# gamby.net
KiCad netlist of a schematic drawn in EAGLE
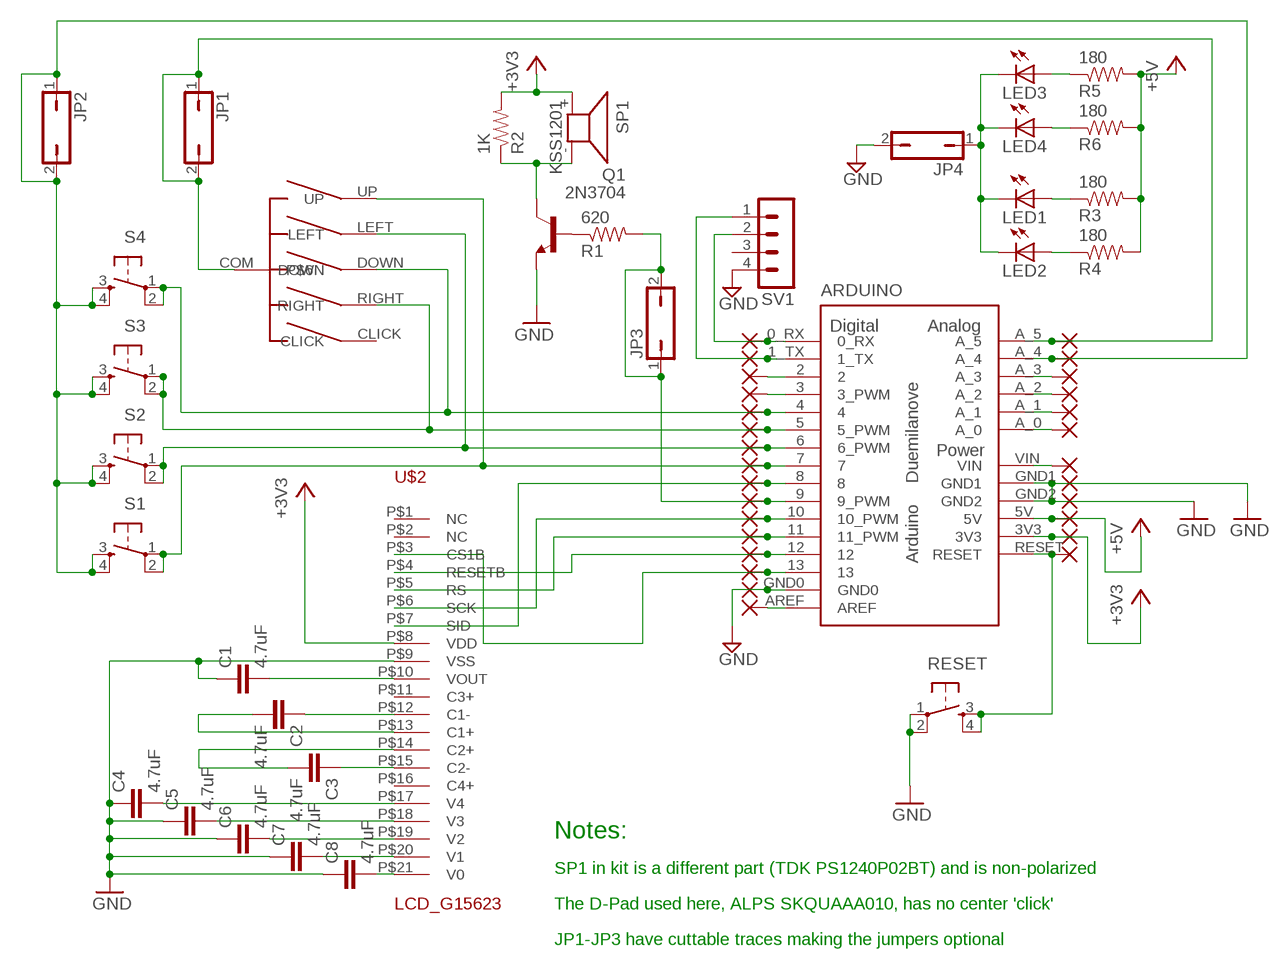
[diagram p0: schematic, sheet 1]

(export (version "E")
  (design (tool "Eeschema 10.0.6"))
  (components
    (comp (ref "ARDUINO")
      (value "ARDUINO-USBLONG_PADS_TEXT")
      (footprint "eagle-import:SHIELD")
      (libsource (lib "eagle-import") (part "ARDUINO-USBLONG_PADS_TEXT"))
    )
    (comp (ref "C1")
      (value "4.7uF")
      (footprint "eagle-import:C2.5-2")
      (libsource (lib "eagle-import") (part "C2.5/2"))
    )
    (comp (ref "C2")
      (value "4.7uF")
      (footprint "eagle-import:C2.5-2")
      (libsource (lib "eagle-import") (part "C2.5/2"))
    )
    (comp (ref "C3")
      (value "4.7uF")
      (footprint "eagle-import:C2.5-2")
      (libsource (lib "eagle-import") (part "C2.5/2"))
    )
    (comp (ref "C4")
      (value "4.7uF")
      (footprint "eagle-import:C2.5-2")
      (libsource (lib "eagle-import") (part "C2.5/2"))
    )
    (comp (ref "C5")
      (value "4.7uF")
      (footprint "eagle-import:C2.5-2")
      (libsource (lib "eagle-import") (part "C2.5/2"))
    )
    (comp (ref "C6")
      (value "4.7uF")
      (footprint "eagle-import:C2.5-2")
      (libsource (lib "eagle-import") (part "C2.5/2"))
    )
    (comp (ref "C7")
      (value "4.7uF")
      (footprint "eagle-import:C2.5-2")
      (libsource (lib "eagle-import") (part "C2.5/2"))
    )
    (comp (ref "C8")
      (value "4.7uF")
      (footprint "eagle-import:C2.5-2")
      (libsource (lib "eagle-import") (part "C2.5/2"))
    )
    (comp (ref "JP1")
      (value "JP1Q")
      (footprint "eagle-import:JP1")
      (libsource (lib "eagle-import") (part "JP1Q"))
    )
    (comp (ref "JP2")
      (value "JP1Q")
      (footprint "eagle-import:JP1")
      (libsource (lib "eagle-import") (part "JP1Q"))
    )
    (comp (ref "JP3")
      (value "JP1Q")
      (footprint "eagle-import:JP1")
      (libsource (lib "eagle-import") (part "JP1Q"))
    )
    (comp (ref "JP4")
      (value "JP1Q")
      (footprint "eagle-import:JP1")
      (libsource (lib "eagle-import") (part "JP1Q"))
    )
    (comp (ref "LED1")
      (value "LEDSMT1206")
      (footprint "eagle-import:1206")
      (libsource (lib "eagle-import") (part "LEDSMT1206"))
    )
    (comp (ref "LED2")
      (value "LEDSMT1206")
      (footprint "eagle-import:1206")
      (libsource (lib "eagle-import") (part "LEDSMT1206"))
    )
    (comp (ref "LED3")
      (value "LEDSMT1206")
      (footprint "eagle-import:1206")
      (libsource (lib "eagle-import") (part "LEDSMT1206"))
    )
    (comp (ref "LED4")
      (value "LEDSMT1206")
      (footprint "eagle-import:1206")
      (libsource (lib "eagle-import") (part "LEDSMT1206"))
    )
    (comp (ref "PAD_3V3")
      (value "WIREPAD1,6/0,9")
      (footprint "eagle-import:1,6_0,9")
      (libsource (lib "eagle-import") (part "WIREPAD1,6/0,9"))
    )
    (comp (ref "PAD_5V")
      (value "WIREPAD1,6/0,9")
      (footprint "eagle-import:1,6_0,9")
      (libsource (lib "eagle-import") (part "WIREPAD1,6/0,9"))
    )
    (comp (ref "PAD_A0")
      (value "WIREPAD1,6/0,9")
      (footprint "eagle-import:1,6_0,9")
      (libsource (lib "eagle-import") (part "WIREPAD1,6/0,9"))
    )
    (comp (ref "PAD_A1")
      (value "WIREPAD1,6/0,9")
      (footprint "eagle-import:1,6_0,9")
      (libsource (lib "eagle-import") (part "WIREPAD1,6/0,9"))
    )
    (comp (ref "PAD_A2")
      (value "WIREPAD1,6/0,9")
      (footprint "eagle-import:1,6_0,9")
      (libsource (lib "eagle-import") (part "WIREPAD1,6/0,9"))
    )
    (comp (ref "PAD_A3")
      (value "WIREPAD1,6/0,9")
      (footprint "eagle-import:1,6_0,9")
      (libsource (lib "eagle-import") (part "WIREPAD1,6/0,9"))
    )
    (comp (ref "PAD_A4")
      (value "WIREPAD1,6/0,9")
      (footprint "eagle-import:1,6_0,9")
      (libsource (lib "eagle-import") (part "WIREPAD1,6/0,9"))
    )
    (comp (ref "PAD_A5")
      (value "WIREPAD1,6/0,9")
      (footprint "eagle-import:1,6_0,9")
      (libsource (lib "eagle-import") (part "WIREPAD1,6/0,9"))
    )
    (comp (ref "PAD_AREF")
      (value "WIREPAD1,6/0,9")
      (footprint "eagle-import:1,6_0,9")
      (libsource (lib "eagle-import") (part "WIREPAD1,6/0,9"))
    )
    (comp (ref "PAD_D2")
      (value "WIREPAD1,6/0,9")
      (footprint "eagle-import:1,6_0,9")
      (libsource (lib "eagle-import") (part "WIREPAD1,6/0,9"))
    )
    (comp (ref "PAD_D3")
      (value "WIREPAD1,6/0,9")
      (footprint "eagle-import:1,6_0,9")
      (libsource (lib "eagle-import") (part "WIREPAD1,6/0,9"))
    )
    (comp (ref "PAD_D4")
      (value "WIREPAD1,6/0,9")
      (footprint "eagle-import:1,6_0,9")
      (libsource (lib "eagle-import") (part "WIREPAD1,6/0,9"))
    )
    (comp (ref "PAD_D5")
      (value "WIREPAD1,6/0,9")
      (footprint "eagle-import:1,6_0,9")
      (libsource (lib "eagle-import") (part "WIREPAD1,6/0,9"))
    )
    (comp (ref "PAD_D6")
      (value "WIREPAD1,6/0,9")
      (footprint "eagle-import:1,6_0,9")
      (libsource (lib "eagle-import") (part "WIREPAD1,6/0,9"))
    )
    (comp (ref "PAD_D7")
      (value "WIREPAD1,6/0,9")
      (footprint "eagle-import:1,6_0,9")
      (libsource (lib "eagle-import") (part "WIREPAD1,6/0,9"))
    )
    (comp (ref "PAD_D8")
      (value "WIREPAD1,6/0,9")
      (footprint "eagle-import:1,6_0,9")
      (libsource (lib "eagle-import") (part "WIREPAD1,6/0,9"))
    )
    (comp (ref "PAD_D9")
      (value "WIREPAD1,6/0,9")
      (footprint "eagle-import:1,6_0,9")
      (libsource (lib "eagle-import") (part "WIREPAD1,6/0,9"))
    )
    (comp (ref "PAD_D10")
      (value "WIREPAD1,6/0,9")
      (footprint "eagle-import:1,6_0,9")
      (libsource (lib "eagle-import") (part "WIREPAD1,6/0,9"))
    )
    (comp (ref "PAD_D11")
      (value "WIREPAD1,6/0,9")
      (footprint "eagle-import:1,6_0,9")
      (libsource (lib "eagle-import") (part "WIREPAD1,6/0,9"))
    )
    (comp (ref "PAD_D12")
      (value "WIREPAD1,6/0,9")
      (footprint "eagle-import:1,6_0,9")
      (libsource (lib "eagle-import") (part "WIREPAD1,6/0,9"))
    )
    (comp (ref "PAD_D13")
      (value "WIREPAD1,6/0,9")
      (footprint "eagle-import:1,6_0,9")
      (libsource (lib "eagle-import") (part "WIREPAD1,6/0,9"))
    )
    (comp (ref "PAD_GND0")
      (value "WIREPAD1,6/0,9")
      (footprint "eagle-import:1,6_0,9")
      (libsource (lib "eagle-import") (part "WIREPAD1,6/0,9"))
    )
    (comp (ref "PAD_GND1")
      (value "WIREPAD1,6/0,9")
      (footprint "eagle-import:1,6_0,9")
      (libsource (lib "eagle-import") (part "WIREPAD1,6/0,9"))
    )
    (comp (ref "PAD_GND2")
      (value "WIREPAD1,6/0,9")
      (footprint "eagle-import:1,6_0,9")
      (libsource (lib "eagle-import") (part "WIREPAD1,6/0,9"))
    )
    (comp (ref "PAD_RESET")
      (value "WIREPAD1,6/0,9")
      (footprint "eagle-import:1,6_0,9")
      (libsource (lib "eagle-import") (part "WIREPAD1,6/0,9"))
    )
    (comp (ref "PAD_RX")
      (value "WIREPAD1,6/0,9")
      (footprint "eagle-import:1,6_0,9")
      (libsource (lib "eagle-import") (part "WIREPAD1,6/0,9"))
    )
    (comp (ref "PAD_TX")
      (value "WIREPAD1,6/0,9")
      (footprint "eagle-import:1,6_0,9")
      (libsource (lib "eagle-import") (part "WIREPAD1,6/0,9"))
    )
    (comp (ref "PAD_VIN")
      (value "WIREPAD1,6/0,9")
      (footprint "eagle-import:1,6_0,9")
      (libsource (lib "eagle-import") (part "WIREPAD1,6/0,9"))
    )
    (comp (ref "Q1")
      (value "2N3704")
      (footprint "eagle-import:TO92")
      (libsource (lib "eagle-import") (part "2N3704"))
    )
    (comp (ref "R1")
      (value "620")
      (footprint "eagle-import:AXIAL-0.3")
      (libsource (lib "eagle-import") (part "RESISTORPTH1"))
    )
    (comp (ref "R2")
      (value "1K")
      (footprint "eagle-import:AXIAL-0.3")
      (libsource (lib "eagle-import") (part "RESISTORPTH1"))
    )
    (comp (ref "R3")
      (value "180")
      (footprint "eagle-import:AXIAL-0.3")
      (libsource (lib "eagle-import") (part "RESISTORPTH1"))
    )
    (comp (ref "R4")
      (value "180")
      (footprint "eagle-import:AXIAL-0.3")
      (libsource (lib "eagle-import") (part "RESISTORPTH1"))
    )
    (comp (ref "R5")
      (value "180")
      (footprint "eagle-import:AXIAL-0.3")
      (libsource (lib "eagle-import") (part "RESISTORPTH1"))
    )
    (comp (ref "R6")
      (value "180")
      (footprint "eagle-import:AXIAL-0.3")
      (libsource (lib "eagle-import") (part "RESISTORPTH1"))
    )
    (comp (ref "RESET")
      (value "TAC_SWITCHPTH")
      (footprint "eagle-import:TACTILE-PTH")
      (libsource (lib "eagle-import") (part "TAC_SWITCHPTH"))
    )
    (comp (ref "S1")
      (value "TAC_SWITCHPTH")
      (footprint "eagle-import:TACTILE-PTH")
      (libsource (lib "eagle-import") (part "TAC_SWITCHPTH"))
    )
    (comp (ref "S2")
      (value "TAC_SWITCHPTH")
      (footprint "eagle-import:TACTILE-PTH")
      (libsource (lib "eagle-import") (part "TAC_SWITCHPTH"))
    )
    (comp (ref "S3")
      (value "TAC_SWITCHPTH")
      (footprint "eagle-import:TACTILE-PTH")
      (libsource (lib "eagle-import") (part "TAC_SWITCHPTH"))
    )
    (comp (ref "S4")
      (value "TAC_SWITCHPTH")
      (footprint "eagle-import:TACTILE-PTH")
      (libsource (lib "eagle-import") (part "TAC_SWITCHPTH"))
    )
    (comp (ref "SP1")
      (value "KSS1201")
      (footprint "eagle-import:KSS1201")
      (libsource (lib "eagle-import") (part "KSS1201"))
    )
    (comp (ref "SV1")
      (value "MA04-1")
      (footprint "eagle-import:MA04-1")
      (libsource (lib "eagle-import") (part "MA04-1"))
    )
    (comp (ref "U$2")
      (value "LCD_G15623")
      (footprint "eagle-import:LCD_G15623")
      (libsource (lib "eagle-import") (part "LCD_G15623"))
    )
    (comp (ref "U$3")
      (value "DEV1")
      (footprint "eagle-import:DIP")
      (libsource (lib "eagle-import") (part "DEV1"))
    )
  )
  (nets
    (net (code "1") (name "+3V3") (class "Default")
      (node (ref "ARDUINO") (pin "3V3") (pinfunction "3V3_3V3") (pintype "power_in"))
      (node (ref "PAD_3V3") (pin "1") (pinfunction "P_1") (pintype "passive"))
      (node (ref "R2") (pin "P$2") (pinfunction "2_P$2") (pintype "passive"))
      (node (ref "SP1") (pin "+") (pinfunction "1_+") (pintype "passive"))
      (node (ref "U$2") (pin "P$8") (pinfunction "VDD_P$8") (pintype "bidirectional"))
    )
    (net (code "2") (name "+5V") (class "Default")
      (node (ref "ARDUINO") (pin "5V") (pinfunction "5V_5V") (pintype "power_in"))
      (node (ref "PAD_5V") (pin "1") (pinfunction "P_1") (pintype "passive"))
      (node (ref "R3") (pin "P$2") (pinfunction "2_P$2") (pintype "passive"))
      (node (ref "R4") (pin "P$2") (pinfunction "2_P$2") (pintype "passive"))
      (node (ref "R5") (pin "P$2") (pinfunction "2_P$2") (pintype "passive"))
      (node (ref "R6") (pin "P$2") (pinfunction "2_P$2") (pintype "passive"))
    )
    (net (code "3") (name "GND") (class "Default")
      (node (ref "ARDUINO") (pin "GND0") (pinfunction "GND0_GND0") (pintype "power_in"))
      (node (ref "ARDUINO") (pin "GND1") (pinfunction "GND1_GND1") (pintype "power_in"))
      (node (ref "ARDUINO") (pin "GND2") (pinfunction "GND2_GND2") (pintype "power_in"))
      (node (ref "C1") (pin "1") (pinfunction "1_1") (pintype "passive"))
      (node (ref "C4") (pin "1") (pinfunction "1_1") (pintype "passive"))
      (node (ref "C5") (pin "1") (pinfunction "1_1") (pintype "passive"))
      (node (ref "C6") (pin "1") (pinfunction "1_1") (pintype "passive"))
      (node (ref "C7") (pin "1") (pinfunction "1_1") (pintype "passive"))
      (node (ref "C8") (pin "1") (pinfunction "1_1") (pintype "passive"))
      (node (ref "JP4") (pin "2") (pinfunction "2_2") (pintype "passive"))
      (node (ref "PAD_GND0") (pin "1") (pinfunction "P_1") (pintype "passive"))
      (node (ref "PAD_GND1") (pin "1") (pinfunction "P_1") (pintype "passive"))
      (node (ref "PAD_GND2") (pin "1") (pinfunction "P_1") (pintype "passive"))
      (node (ref "Q1") (pin "3") (pinfunction "E_3") (pintype "passive"))
      (node (ref "RESET") (pin "1") (pinfunction "1_1") (pintype "passive"))
      (node (ref "RESET") (pin "2") (pinfunction "2_2") (pintype "passive"))
      (node (ref "SV1") (pin "4") (pinfunction "4_4") (pintype "passive"))
      (node (ref "U$2") (pin "P$9") (pinfunction "VSS_P$9") (pintype "bidirectional"))
    )
    (net (code "4") (name "Net-(ARDUINO-3_PWM)") (class "Default")
      (node (ref "ARDUINO") (pin "3") (pinfunction "3_PWM_3") (pintype "bidirectional"))
      (node (ref "PAD_D3") (pin "1") (pinfunction "P_1") (pintype "passive"))
    )
    (net (code "5") (name "Net-(ARDUINO-5_PWM)") (class "Default")
      (node (ref "ARDUINO") (pin "5") (pinfunction "5_PWM_5") (pintype "bidirectional"))
      (node (ref "PAD_D5") (pin "1") (pinfunction "P_1") (pintype "passive"))
      (node (ref "S3") (pin "1") (pinfunction "1_1") (pintype "passive"))
      (node (ref "S3") (pin "2") (pinfunction "2_2") (pintype "passive"))
      (node (ref "U$3") (pin "RIGHT") (pinfunction "RIGHT_RIGHT") (pintype "bidirectional"))
    )
    (net (code "6") (name "Net-(ARDUINO-6_PWM)") (class "Default")
      (node (ref "ARDUINO") (pin "6") (pinfunction "6_PWM_6") (pintype "bidirectional"))
      (node (ref "PAD_D6") (pin "1") (pinfunction "P_1") (pintype "passive"))
      (node (ref "S2") (pin "1") (pinfunction "1_1") (pintype "passive"))
      (node (ref "S2") (pin "2") (pinfunction "2_2") (pintype "passive"))
      (node (ref "U$3") (pin "LEFT") (pinfunction "LEFT_LEFT") (pintype "bidirectional"))
    )
    (net (code "7") (name "Net-(ARDUINO-9_PWM)") (class "Default")
      (node (ref "ARDUINO") (pin "9") (pinfunction "9_PWM_9") (pintype "bidirectional"))
      (node (ref "JP3") (pin "1") (pinfunction "1_1") (pintype "passive"))
      (node (ref "JP3") (pin "2") (pinfunction "2_2") (pintype "passive"))
      (node (ref "PAD_D9") (pin "1") (pinfunction "P_1") (pintype "passive"))
      (node (ref "R1") (pin "P$2") (pinfunction "2_P$2") (pintype "passive"))
    )
    (net (code "8") (name "Net-(ARDUINO-10_PWM)") (class "Default")
      (node (ref "ARDUINO") (pin "10") (pinfunction "10_PWM_10") (pintype "bidirectional"))
      (node (ref "PAD_D10") (pin "1") (pinfunction "P_1") (pintype "passive"))
      (node (ref "U$2") (pin "P$6") (pinfunction "SCK_P$6") (pintype "bidirectional"))
    )
    (net (code "9") (name "Net-(ARDUINO-11_PWM)") (class "Default")
      (node (ref "ARDUINO") (pin "11") (pinfunction "11_PWM_11") (pintype "bidirectional"))
      (node (ref "PAD_D11") (pin "1") (pinfunction "P_1") (pintype "passive"))
      (node (ref "U$2") (pin "P$5") (pinfunction "RS_P$5") (pintype "bidirectional"))
    )
    (net (code "10") (name "Net-(JP4-Pad1)") (class "Default")
      (node (ref "JP4") (pin "1") (pinfunction "1_1") (pintype "passive"))
      (node (ref "LED1") (pin "C") (pinfunction "C_C") (pintype "passive"))
      (node (ref "LED2") (pin "C") (pinfunction "C_C") (pintype "passive"))
      (node (ref "LED3") (pin "C") (pinfunction "C_C") (pintype "passive"))
      (node (ref "LED4") (pin "C") (pinfunction "C_C") (pintype "passive"))
    )
    (net (code "11") (name "Net-(PAD_A0-P)") (class "Default")
      (node (ref "ARDUINO") (pin "A_0") (pinfunction "A_0_A_0") (pintype "input"))
      (node (ref "PAD_A0") (pin "1") (pinfunction "P_1") (pintype "passive"))
    )
    (net (code "12") (name "Net-(PAD_A1-P)") (class "Default")
      (node (ref "ARDUINO") (pin "A_1") (pinfunction "A_1_A_1") (pintype "input"))
      (node (ref "PAD_A1") (pin "1") (pinfunction "P_1") (pintype "passive"))
    )
    (net (code "13") (name "Net-(PAD_A2-P)") (class "Default")
      (node (ref "ARDUINO") (pin "A_2") (pinfunction "A_2_A_2") (pintype "input"))
      (node (ref "PAD_A2") (pin "1") (pinfunction "P_1") (pintype "passive"))
    )
    (net (code "14") (name "Net-(PAD_A3-P)") (class "Default")
      (node (ref "ARDUINO") (pin "A_3") (pinfunction "A_3_A_3") (pintype "input"))
      (node (ref "PAD_A3") (pin "1") (pinfunction "P_1") (pintype "passive"))
    )
    (net (code "15") (name "Net-(PAD_A4-P)") (class "Default")
      (node (ref "ARDUINO") (pin "A_4") (pinfunction "A_4_A_4") (pintype "input"))
      (node (ref "JP2") (pin "1") (pinfunction "1_1") (pintype "passive"))
      (node (ref "JP2") (pin "2") (pinfunction "2_2") (pintype "passive"))
      (node (ref "PAD_A4") (pin "1") (pinfunction "P_1") (pintype "passive"))
      (node (ref "S1") (pin "3") (pinfunction "3_3") (pintype "passive"))
      (node (ref "S1") (pin "4") (pinfunction "4_4") (pintype "passive"))
      (node (ref "S2") (pin "3") (pinfunction "3_3") (pintype "passive"))
      (node (ref "S2") (pin "4") (pinfunction "4_4") (pintype "passive"))
      (node (ref "S3") (pin "3") (pinfunction "3_3") (pintype "passive"))
      (node (ref "S3") (pin "4") (pinfunction "4_4") (pintype "passive"))
      (node (ref "S4") (pin "3") (pinfunction "3_3") (pintype "passive"))
      (node (ref "S4") (pin "4") (pinfunction "4_4") (pintype "passive"))
    )
    (net (code "16") (name "Net-(PAD_A5-P)") (class "Default")
      (node (ref "ARDUINO") (pin "A_5") (pinfunction "A_5_A_5") (pintype "input"))
      (node (ref "JP1") (pin "1") (pinfunction "1_1") (pintype "passive"))
      (node (ref "JP1") (pin "2") (pinfunction "2_2") (pintype "passive"))
      (node (ref "PAD_A5") (pin "1") (pinfunction "P_1") (pintype "passive"))
      (node (ref "U$3") (pin "COM") (pinfunction "P$6_COM") (pintype "bidirectional"))
    )
    (net (code "17") (name "Net-(PAD_AREF-P)") (class "Default")
      (node (ref "ARDUINO") (pin "AREF") (pinfunction "AREF_AREF") (pintype "bidirectional"))
      (node (ref "PAD_AREF") (pin "1") (pinfunction "P_1") (pintype "passive"))
    )
    (net (code "18") (name "Net-(PAD_D2-P)") (class "Default")
      (node (ref "ARDUINO") (pin "2") (pinfunction "2_2") (pintype "bidirectional"))
      (node (ref "PAD_D2") (pin "1") (pinfunction "P_1") (pintype "passive"))
    )
    (net (code "19") (name "Net-(PAD_D4-P)") (class "Default")
      (node (ref "ARDUINO") (pin "4") (pinfunction "4_4") (pintype "bidirectional"))
      (node (ref "PAD_D4") (pin "1") (pinfunction "P_1") (pintype "passive"))
      (node (ref "S4") (pin "1") (pinfunction "1_1") (pintype "passive"))
      (node (ref "S4") (pin "2") (pinfunction "2_2") (pintype "passive"))
      (node (ref "U$3") (pin "DOWN") (pinfunction "DOWN_DOWN") (pintype "bidirectional"))
    )
    (net (code "20") (name "Net-(PAD_D7-P)") (class "Default")
      (node (ref "ARDUINO") (pin "7") (pinfunction "7_7") (pintype "bidirectional"))
      (node (ref "PAD_D7") (pin "1") (pinfunction "P_1") (pintype "passive"))
      (node (ref "S1") (pin "1") (pinfunction "1_1") (pintype "passive"))
      (node (ref "S1") (pin "2") (pinfunction "2_2") (pintype "passive"))
      (node (ref "U$3") (pin "UP") (pinfunction "UP_UP") (pintype "bidirectional"))
    )
    (net (code "21") (name "Net-(PAD_D8-P)") (class "Default")
      (node (ref "ARDUINO") (pin "8") (pinfunction "8_8") (pintype "bidirectional"))
      (node (ref "PAD_D8") (pin "1") (pinfunction "P_1") (pintype "passive"))
      (node (ref "U$2") (pin "P$7") (pinfunction "SID_P$7") (pintype "bidirectional"))
    )
    (net (code "22") (name "Net-(PAD_D12-P)") (class "Default")
      (node (ref "ARDUINO") (pin "12") (pinfunction "12_12") (pintype "bidirectional"))
      (node (ref "PAD_D12") (pin "1") (pinfunction "P_1") (pintype "passive"))
      (node (ref "U$2") (pin "P$4") (pinfunction "RESETB_P$4") (pintype "bidirectional"))
    )
    (net (code "23") (name "Net-(PAD_D13-P)") (class "Default")
      (node (ref "ARDUINO") (pin "13") (pinfunction "13_13") (pintype "bidirectional"))
      (node (ref "PAD_D13") (pin "1") (pinfunction "P_1") (pintype "passive"))
      (node (ref "U$2") (pin "P$3") (pinfunction "CS1B_P$3") (pintype "bidirectional"))
    )
    (net (code "24") (name "Net-(PAD_RESET-P)") (class "Default")
      (node (ref "ARDUINO") (pin "RESET") (pinfunction "RESET_RESET") (pintype "input"))
      (node (ref "PAD_RESET") (pin "1") (pinfunction "P_1") (pintype "passive"))
      (node (ref "RESET") (pin "3") (pinfunction "3_3") (pintype "passive"))
      (node (ref "RESET") (pin "4") (pinfunction "4_4") (pintype "passive"))
    )
    (net (code "25") (name "Net-(PAD_RX-P)") (class "Default")
      (node (ref "ARDUINO") (pin "0_RX") (pinfunction "0_RX_0_RX") (pintype "bidirectional"))
      (node (ref "PAD_RX") (pin "1") (pinfunction "P_1") (pintype "passive"))
      (node (ref "SV1") (pin "2") (pinfunction "2_2") (pintype "passive"))
    )
    (net (code "26") (name "Net-(PAD_TX-P)") (class "Default")
      (node (ref "ARDUINO") (pin "1_TX") (pinfunction "1_TX_1_TX") (pintype "bidirectional"))
      (node (ref "PAD_TX") (pin "1") (pinfunction "P_1") (pintype "passive"))
      (node (ref "SV1") (pin "1") (pinfunction "1_1") (pintype "passive"))
    )
    (net (code "27") (name "Net-(PAD_VIN-P)") (class "Default")
      (node (ref "ARDUINO") (pin "VIN") (pinfunction "VIN_VIN") (pintype "power_in"))
      (node (ref "PAD_VIN") (pin "1") (pinfunction "P_1") (pintype "passive"))
    )
    (net (code "28") (name "Net-(Q1-B)") (class "Default")
      (node (ref "Q1") (pin "1") (pinfunction "B_1") (pintype "passive"))
      (node (ref "R1") (pin "P$1") (pinfunction "1_P$1") (pintype "passive"))
    )
    (net (code "29") (name "Net-(Q1-C)") (class "Default")
      (node (ref "Q1") (pin "2") (pinfunction "C_2") (pintype "passive"))
      (node (ref "R2") (pin "P$1") (pinfunction "1_P$1") (pintype "passive"))
      (node (ref "SP1") (pin "-") (pinfunction "2_-") (pintype "passive"))
    )
    (net (code "30") (name "Net-(R3-1)") (class "Default")
      (node (ref "LED1") (pin "A") (pinfunction "A_A") (pintype "passive"))
      (node (ref "R3") (pin "P$1") (pinfunction "1_P$1") (pintype "passive"))
    )
    (net (code "31") (name "Net-(R4-1)") (class "Default")
      (node (ref "LED2") (pin "A") (pinfunction "A_A") (pintype "passive"))
      (node (ref "R4") (pin "P$1") (pinfunction "1_P$1") (pintype "passive"))
    )
    (net (code "32") (name "Net-(R5-1)") (class "Default")
      (node (ref "LED3") (pin "A") (pinfunction "A_A") (pintype "passive"))
      (node (ref "R5") (pin "P$1") (pinfunction "1_P$1") (pintype "passive"))
    )
    (net (code "33") (name "Net-(R6-1)") (class "Default")
      (node (ref "LED4") (pin "A") (pinfunction "A_A") (pintype "passive"))
      (node (ref "R6") (pin "P$1") (pinfunction "1_P$1") (pintype "passive"))
    )
    (net (code "34") (name "Net-(U$2-C1+)") (class "Default")
      (node (ref "C2") (pin "2") (pinfunction "2_2") (pintype "passive"))
      (node (ref "U$2") (pin "P$13") (pinfunction "C1+_P$13") (pintype "bidirectional"))
    )
    (net (code "35") (name "Net-(U$2-C1-)") (class "Default")
      (node (ref "C2") (pin "1") (pinfunction "1_1") (pintype "passive"))
      (node (ref "U$2") (pin "P$12") (pinfunction "C1-_P$12") (pintype "bidirectional"))
    )
    (net (code "36") (name "Net-(U$2-C2+)") (class "Default")
      (node (ref "C3") (pin "2") (pinfunction "2_2") (pintype "passive"))
      (node (ref "U$2") (pin "P$14") (pinfunction "C2+_P$14") (pintype "bidirectional"))
    )
    (net (code "37") (name "Net-(U$2-C2-)") (class "Default")
      (node (ref "C3") (pin "1") (pinfunction "1_1") (pintype "passive"))
      (node (ref "U$2") (pin "P$15") (pinfunction "C2-_P$15") (pintype "bidirectional"))
    )
    (net (code "38") (name "Net-(U$2-V0)") (class "Default")
      (node (ref "C8") (pin "2") (pinfunction "2_2") (pintype "passive"))
      (node (ref "U$2") (pin "P$21") (pinfunction "V0_P$21") (pintype "bidirectional"))
    )
    (net (code "39") (name "Net-(U$2-V1)") (class "Default")
      (node (ref "C7") (pin "2") (pinfunction "2_2") (pintype "passive"))
      (node (ref "U$2") (pin "P$20") (pinfunction "V1_P$20") (pintype "bidirectional"))
    )
    (net (code "40") (name "Net-(U$2-V2)") (class "Default")
      (node (ref "C6") (pin "2") (pinfunction "2_2") (pintype "passive"))
      (node (ref "U$2") (pin "P$19") (pinfunction "V2_P$19") (pintype "bidirectional"))
    )
    (net (code "41") (name "Net-(U$2-V3)") (class "Default")
      (node (ref "C5") (pin "2") (pinfunction "2_2") (pintype "passive"))
      (node (ref "U$2") (pin "P$18") (pinfunction "V3_P$18") (pintype "bidirectional"))
    )
    (net (code "42") (name "Net-(U$2-V4)") (class "Default")
      (node (ref "C4") (pin "2") (pinfunction "2_2") (pintype "passive"))
      (node (ref "U$2") (pin "P$17") (pinfunction "V4_P$17") (pintype "bidirectional"))
    )
    (net (code "43") (name "Net-(U$2-VOUT)") (class "Default")
      (node (ref "C1") (pin "2") (pinfunction "2_2") (pintype "passive"))
      (node (ref "U$2") (pin "P$10") (pinfunction "VOUT_P$10") (pintype "bidirectional"))
    )
    (net (code "44") (name "unconnected-(SV1-Pad3)") (class "Default")
      (node (ref "SV1") (pin "3") (pinfunction "3_3") (pintype "passive"))
    )
    (net (code "45") (name "unconnected-(U$2-C3+-PadP$11)") (class "Default")
      (node (ref "U$2") (pin "P$11") (pinfunction "C3+_P$11") (pintype "bidirectional"))
    )
    (net (code "46") (name "unconnected-(U$2-C4+-PadP$16)") (class "Default")
      (node (ref "U$2") (pin "P$16") (pinfunction "C4+_P$16") (pintype "bidirectional"))
    )
    (net (code "47") (name "unconnected-(U$2-NC-PadP$1)") (class "Default")
      (node (ref "U$2") (pin "P$1") (pinfunction "NC_P$1") (pintype "bidirectional"))
    )
    (net (code "48") (name "unconnected-(U$2-NC-PadP$2)") (class "Default")
      (node (ref "U$2") (pin "P$2") (pinfunction "NC_P$2") (pintype "bidirectional"))
    )
    (net (code "49") (name "unconnected-(U$3-PadCLICK)") (class "Default")
      (node (ref "U$3") (pin "CLICK") (pinfunction "CLICK_CLICK") (pintype "bidirectional"))
    )
  )
)
